# 1-wire_adapter_barebones.net
KiCad netlist of a schematic drawn in Altium Designer
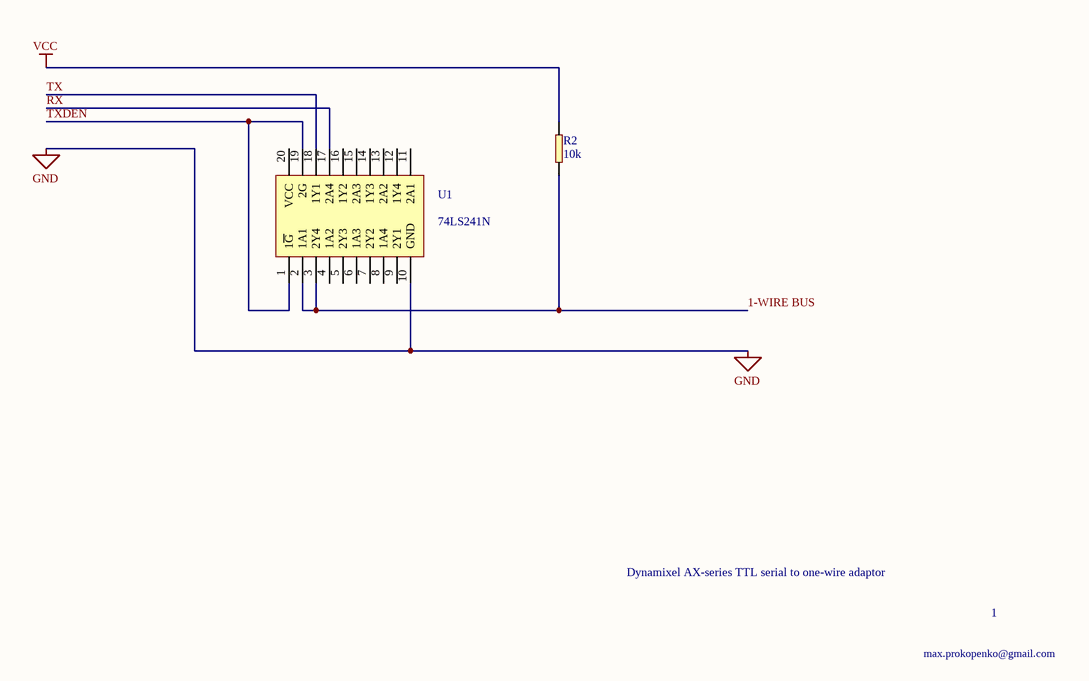
[diagram p0: 1-wire adapter barebones.SchDoc]

(export (version "E")
  (design (tool "Eeschema 10.0.6"))
  (components
    (comp (ref "R2")
      (value "R 10k")
      (footprint "0603")
      (fields (field (name "R") "10k"))
      (libsource (lib "RLC") (part "R 10k"))
    )
    (comp (ref "U1") (value "74LS241N") (libsource (lib "OpBots") (part "74LS241N")))
  )
  (nets
    (net (code "1") (name "/1-WIRE BUS") (class "Default")
      (node (ref "R2") (pin "2") (pintype "passive"))
      (node (ref "U1") (pin "2") (pinfunction "1A1_2") (pintype "passive"))
      (node (ref "U1") (pin "3") (pinfunction "2Y4_3") (pintype "passive"))
    )
    (net (code "2") (name "/RX") (class "Default")
      (node (ref "U1") (pin "17") (pinfunction "2A4_17") (pintype "passive"))
    )
    (net (code "3") (name "/TX") (class "Default")
      (node (ref "U1") (pin "18") (pinfunction "1Y1_18") (pintype "passive"))
    )
    (net (code "4") (name "/TXDEN") (class "Default")
      (node (ref "U1") (pin "1") (pinfunction "1~{G}_1") (pintype "passive"))
      (node (ref "U1") (pin "19") (pinfunction "2G_19") (pintype "passive"))
    )
    (net (code "5") (name "GND") (class "Default")
      (node (ref "U1") (pin "10") (pinfunction "GND_10") (pintype "passive"))
    )
    (net (code "6") (name "VCC") (class "Default") (node (ref "R2") (pin "1") (pintype "passive")))
    (net (code "7") (name "unconnected-(U1-1A2-Pad4)") (class "Default")
      (node (ref "U1") (pin "4") (pinfunction "1A2_4") (pintype "passive"))
    )
    (net (code "8") (name "unconnected-(U1-1A3-Pad6)") (class "Default")
      (node (ref "U1") (pin "6") (pinfunction "1A3_6") (pintype "passive"))
    )
    (net (code "9") (name "unconnected-(U1-1A4-Pad8)") (class "Default")
      (node (ref "U1") (pin "8") (pinfunction "1A4_8") (pintype "passive"))
    )
    (net (code "10") (name "unconnected-(U1-1Y2-Pad16)") (class "Default")
      (node (ref "U1") (pin "16") (pinfunction "1Y2_16") (pintype "passive"))
    )
    (net (code "11") (name "unconnected-(U1-1Y3-Pad14)") (class "Default")
      (node (ref "U1") (pin "14") (pinfunction "1Y3_14") (pintype "passive"))
    )
    (net (code "12") (name "unconnected-(U1-1Y4-Pad12)") (class "Default")
      (node (ref "U1") (pin "12") (pinfunction "1Y4_12") (pintype "passive"))
    )
    (net (code "13") (name "unconnected-(U1-2A1-Pad11)") (class "Default")
      (node (ref "U1") (pin "11") (pinfunction "2A1_11") (pintype "passive"))
    )
    (net (code "14") (name "unconnected-(U1-2A2-Pad13)") (class "Default")
      (node (ref "U1") (pin "13") (pinfunction "2A2_13") (pintype "passive"))
    )
    (net (code "15") (name "unconnected-(U1-2A3-Pad15)") (class "Default")
      (node (ref "U1") (pin "15") (pinfunction "2A3_15") (pintype "passive"))
    )
    (net (code "16") (name "unconnected-(U1-2Y1-Pad9)") (class "Default")
      (node (ref "U1") (pin "9") (pinfunction "2Y1_9") (pintype "passive"))
    )
    (net (code "17") (name "unconnected-(U1-2Y2-Pad7)") (class "Default")
      (node (ref "U1") (pin "7") (pinfunction "2Y2_7") (pintype "passive"))
    )
    (net (code "18") (name "unconnected-(U1-2Y3-Pad5)") (class "Default")
      (node (ref "U1") (pin "5") (pinfunction "2Y3_5") (pintype "passive"))
    )
    (net (code "19") (name "unconnected-(U1-VCC-Pad20)") (class "Default")
      (node (ref "U1") (pin "20") (pinfunction "VCC_20") (pintype "passive"))
    )
  )
)
